# wt12_uart_breakout_board_v21.net
KiCad netlist of a schematic drawn in EAGLE
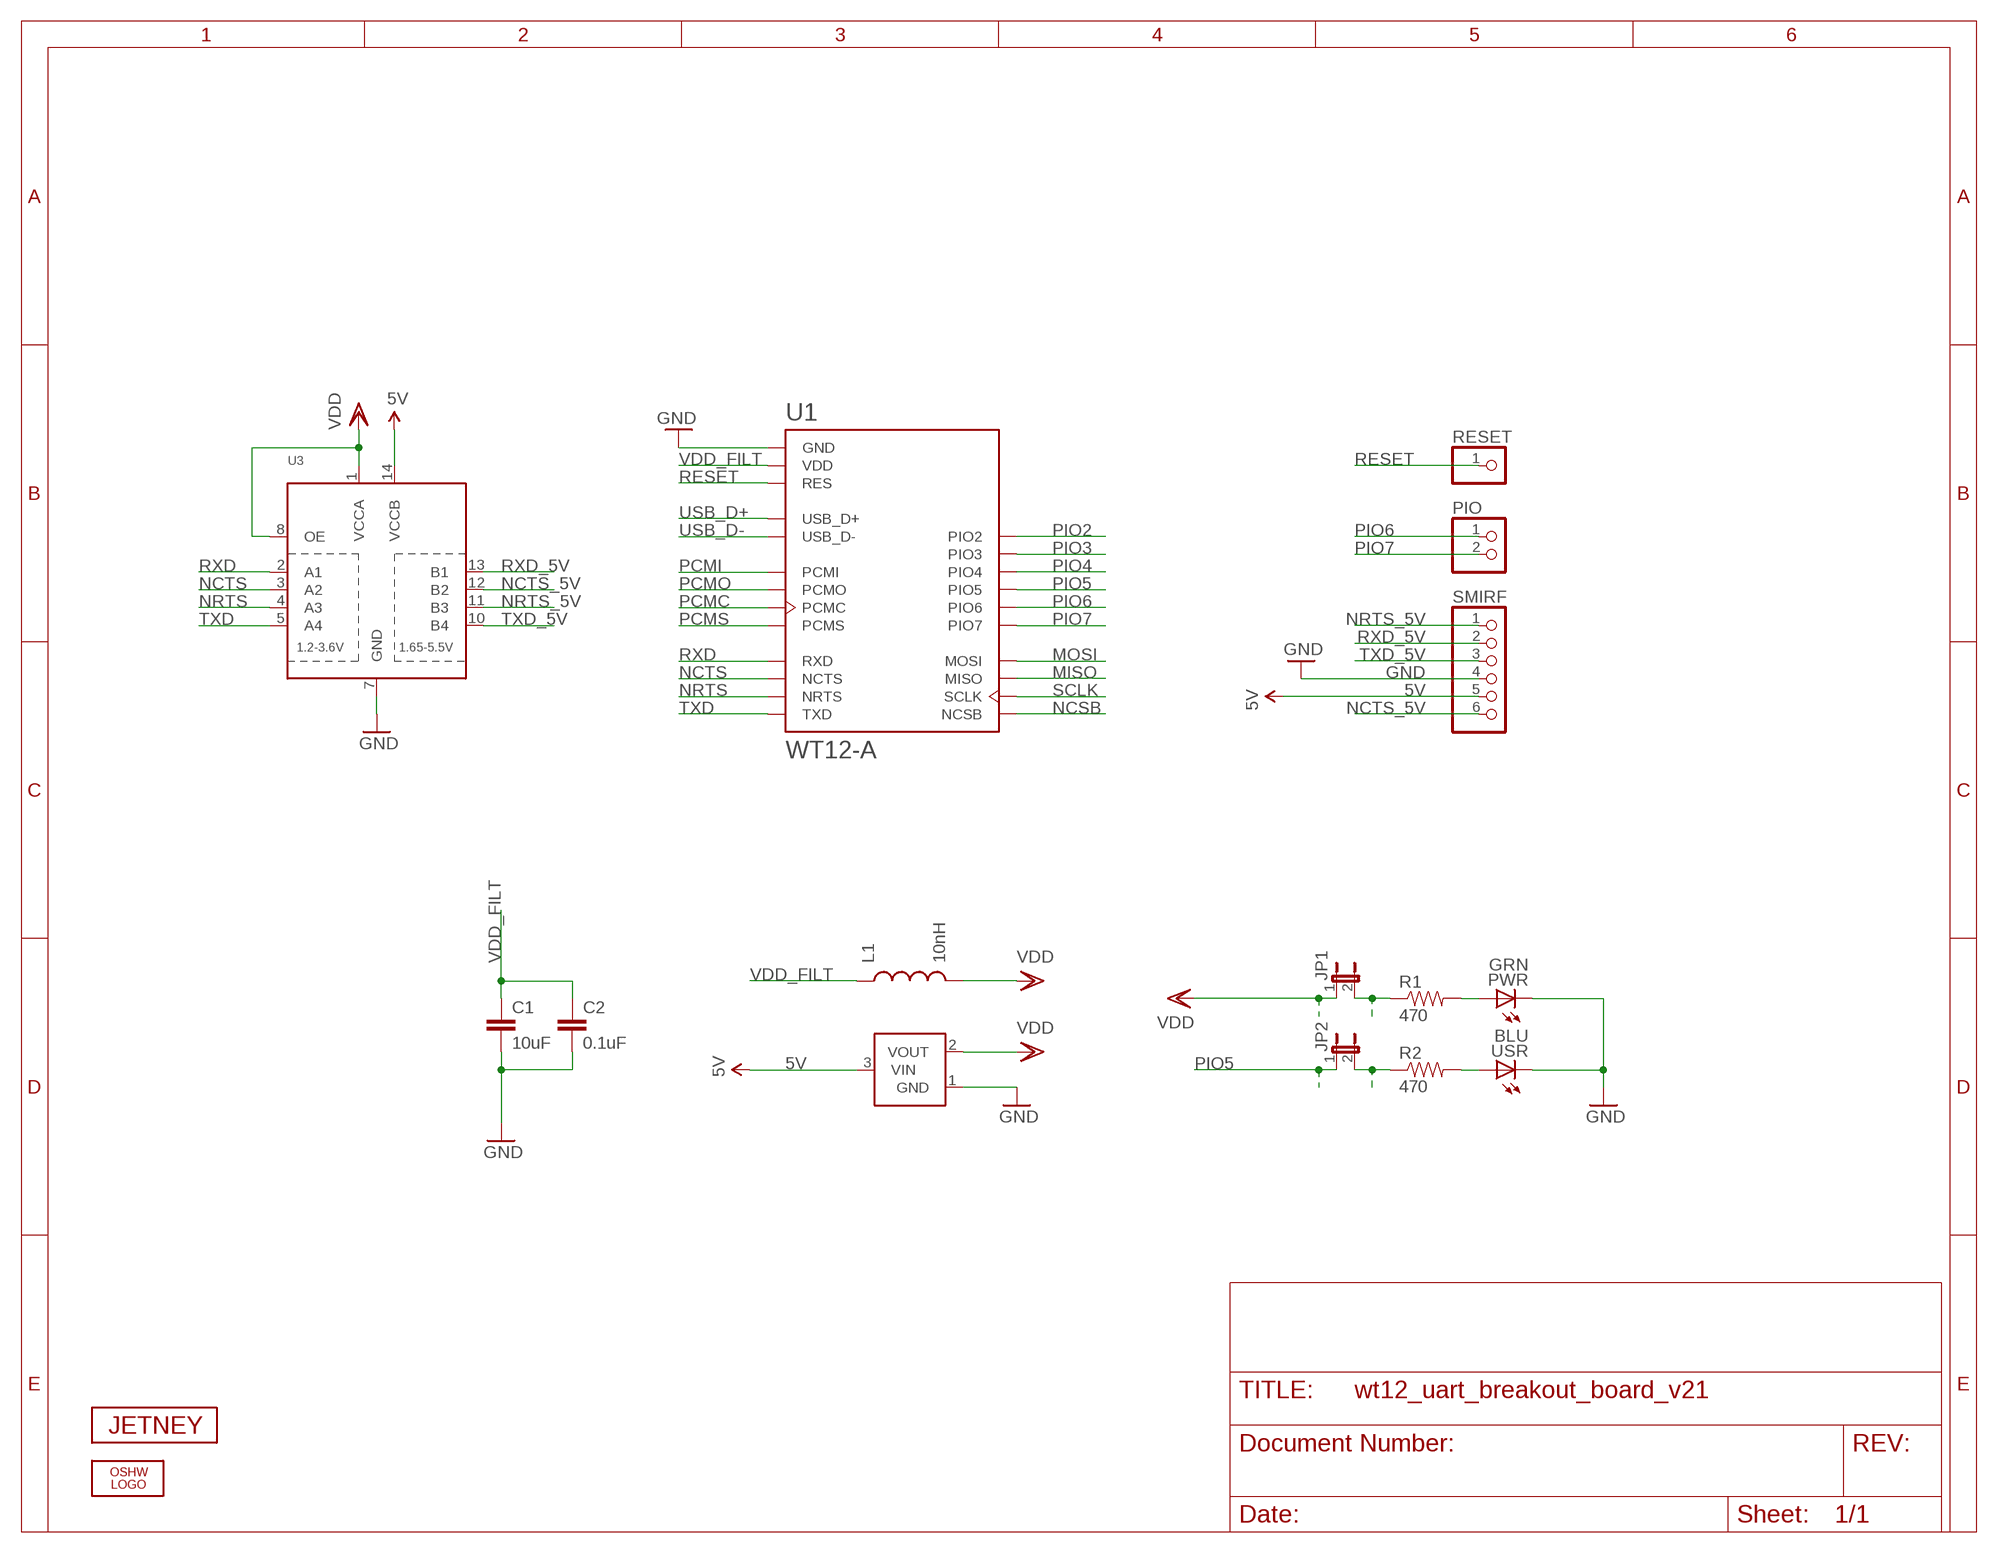
[diagram p0: schematic, sheet 1]

(export (version "E")
  (design (tool "Eeschema 10.0.6"))
  (components
    (comp (ref "C1")
      (value "10uF")
      (footprint "eagle-import:0603-CAP")
      (libsource (lib "eagle-import") (part "CAP0603-CAP"))
    )
    (comp (ref "C2")
      (value "0.1uF")
      (footprint "eagle-import:0603-CAP")
      (libsource (lib "eagle-import") (part "CAP0603-CAP"))
    )
    (comp (ref "JP1")
      (value "JUMPER-2SMD-NC")
      (footprint "eagle-import:SJ_2S")
      (libsource (lib "eagle-import") (part "JUMPER-2SMD-NC"))
    )
    (comp (ref "JP2")
      (value "JUMPER-2SMD-NC")
      (footprint "eagle-import:SJ_2S")
      (libsource (lib "eagle-import") (part "JUMPER-2SMD-NC"))
    )
    (comp (ref "L1")
      (value "10nH")
      (footprint "eagle-import:0603")
      (libsource (lib "eagle-import") (part "INDUCTOR0603"))
    )
    (comp (ref "LOGO1")
      (value "OSHW_LOGO_FILLX0070-NT")
      (footprint "eagle-import:OSHW_FILLX70_NOTEXT")
      (libsource (lib "eagle-import") (part "OSHW_LOGO_FILLX0070-NT"))
    )
    (comp (ref "PIO")
      (value "PINHD-1X2")
      (footprint "eagle-import:1X02")
      (libsource (lib "eagle-import") (part "PINHD-1X2"))
    )
    (comp (ref "PWR")
      (value "GRN")
      (footprint "eagle-import:CHIPLED_0805")
      (libsource (lib "eagle-import") (part "LEDCHIPLED_0805"))
    )
    (comp (ref "R1")
      (value "470")
      (footprint "eagle-import:0603-RES")
      (libsource (lib "eagle-import") (part "RESISTOR0603-RES"))
    )
    (comp (ref "R2")
      (value "470")
      (footprint "eagle-import:0603-RES")
      (libsource (lib "eagle-import") (part "RESISTOR0603-RES"))
    )
    (comp (ref "RESET")
      (value "PINHD-1X1")
      (footprint "eagle-import:1X01")
      (libsource (lib "eagle-import") (part "PINHD-1X1"))
    )
    (comp (ref "SMIRF")
      (value "PINHD-1X6")
      (footprint "eagle-import:1X06")
      (libsource (lib "eagle-import") (part "PINHD-1X6"))
    )
    (comp (ref "U$4")
      (value "JETNEY-LOGO-12")
      (footprint "eagle-import:JETNEY-LOGO-12")
      (libsource (lib "eagle-import") (part "JETNEY-LOGO-12"))
    )
    (comp (ref "U1")
      (value "WT12-A")
      (footprint "eagle-import:WT12-A")
      (libsource (lib "eagle-import") (part "WT12-A"))
    )
    (comp (ref "U2")
      (value "MCP1700")
      (footprint "eagle-import:SOT23-3")
      (libsource (lib "eagle-import") (part "MCP1700"))
    )
    (comp (ref "U3")
      (value "TXB0104PWR")
      (footprint "eagle-import:TSSOP14")
      (libsource (lib "eagle-import") (part "TXB0104PWR"))
    )
    (comp (ref "USR")
      (value "BLU")
      (footprint "eagle-import:CHIPLED_0805")
      (libsource (lib "eagle-import") (part "LEDCHIPLED_0805"))
    )
  )
  (nets
    (net (code "1") (name "/MISO") (class "Default")
      (node (ref "U1") (pin "MISO") (pinfunction "MISO_MISO") (pintype "output"))
    )
    (net (code "2") (name "/MOSI") (class "Default")
      (node (ref "U1") (pin "MOSI") (pinfunction "MOSI_MOSI") (pintype "input"))
    )
    (net (code "3") (name "/NCSB") (class "Default")
      (node (ref "U1") (pin "NCSB") (pinfunction "NCSB_NCSB") (pintype "input"))
    )
    (net (code "4") (name "/NCTS") (class "Default")
      (node (ref "U1") (pin "NCTS") (pinfunction "NCTS_NCTS") (pintype "input"))
      (node (ref "U3") (pin "3") (pinfunction "A2_3") (pintype "bidirectional"))
    )
    (net (code "5") (name "/NCTS_5V") (class "Default")
      (node (ref "SMIRF") (pin "6") (pinfunction "6_6") (pintype "passive"))
      (node (ref "U3") (pin "12") (pinfunction "B2_12") (pintype "bidirectional"))
    )
    (net (code "6") (name "/NRTS") (class "Default")
      (node (ref "U1") (pin "NRTS") (pinfunction "NRTS_NRTS") (pintype "output"))
      (node (ref "U3") (pin "4") (pinfunction "A3_4") (pintype "bidirectional"))
    )
    (net (code "7") (name "/NRTS_5V") (class "Default")
      (node (ref "SMIRF") (pin "1") (pinfunction "1_1") (pintype "passive"))
      (node (ref "U3") (pin "11") (pinfunction "B3_11") (pintype "bidirectional"))
    )
    (net (code "8") (name "/PCMC") (class "Default")
      (node (ref "U1") (pin "PCMC") (pinfunction "PCMC_PCMC") (pintype "bidirectional"))
    )
    (net (code "9") (name "/PCMI") (class "Default")
      (node (ref "U1") (pin "PCMI") (pinfunction "PCMI_PCMI") (pintype "input"))
    )
    (net (code "10") (name "/PCMO") (class "Default")
      (node (ref "U1") (pin "PCMO") (pinfunction "PCMO_PCMO") (pintype "output"))
    )
    (net (code "11") (name "/PCMS") (class "Default")
      (node (ref "U1") (pin "PCMS") (pinfunction "PCMS_PCMS") (pintype "bidirectional"))
    )
    (net (code "12") (name "/PIO2") (class "Default")
      (node (ref "U1") (pin "PIO2") (pinfunction "PIO2_PIO2") (pintype "bidirectional"))
    )
    (net (code "13") (name "/PIO3") (class "Default")
      (node (ref "U1") (pin "PIO3") (pinfunction "PIO3_PIO3") (pintype "bidirectional"))
    )
    (net (code "14") (name "/PIO4") (class "Default")
      (node (ref "U1") (pin "PIO4") (pinfunction "PIO4_PIO4") (pintype "bidirectional"))
    )
    (net (code "15") (name "/PIO5") (class "Default")
      (node (ref "JP2") (pin "1") (pinfunction "1_1") (pintype "passive"))
      (node (ref "U1") (pin "PIO5") (pinfunction "PIO5_PIO5") (pintype "bidirectional"))
    )
    (net (code "16") (name "/PIO6") (class "Default")
      (node (ref "PIO") (pin "1") (pinfunction "1_1") (pintype "passive"))
      (node (ref "U1") (pin "PIO6") (pinfunction "PIO6_PIO6") (pintype "bidirectional"))
    )
    (net (code "17") (name "/PIO7") (class "Default")
      (node (ref "PIO") (pin "2") (pinfunction "2_2") (pintype "passive"))
      (node (ref "U1") (pin "PIO7") (pinfunction "PIO7_PIO7") (pintype "bidirectional"))
    )
    (net (code "18") (name "/RESET") (class "Default")
      (node (ref "RESET") (pin "1") (pinfunction "1_1") (pintype "passive"))
      (node (ref "U1") (pin "RES") (pinfunction "RES_RES") (pintype "input"))
    )
    (net (code "19") (name "/RXD") (class "Default")
      (node (ref "U1") (pin "RXD") (pinfunction "RXD_RXD") (pintype "input"))
      (node (ref "U3") (pin "2") (pinfunction "A1_2") (pintype "bidirectional"))
    )
    (net (code "20") (name "/RXD_5V") (class "Default")
      (node (ref "SMIRF") (pin "2") (pinfunction "2_2") (pintype "passive"))
      (node (ref "U3") (pin "13") (pinfunction "B1_13") (pintype "bidirectional"))
    )
    (net (code "21") (name "/SCLK") (class "Default")
      (node (ref "U1") (pin "SCLK") (pinfunction "SCLK_SCLK") (pintype "input"))
    )
    (net (code "22") (name "/TXD") (class "Default")
      (node (ref "U1") (pin "TXD") (pinfunction "TXD_TXD") (pintype "output"))
      (node (ref "U3") (pin "5") (pinfunction "A4_5") (pintype "bidirectional"))
    )
    (net (code "23") (name "/TXD_5V") (class "Default")
      (node (ref "SMIRF") (pin "3") (pinfunction "3_3") (pintype "passive"))
      (node (ref "U3") (pin "10") (pinfunction "B4_10") (pintype "bidirectional"))
    )
    (net (code "24") (name "/USB_D+") (class "Default")
      (node (ref "U1") (pin "USB_D+") (pinfunction "USB_D+_USB_D+") (pintype "bidirectional"))
    )
    (net (code "25") (name "/USB_D-") (class "Default")
      (node (ref "U1") (pin "USB_D-") (pinfunction "USB_D-_USB_D-") (pintype "bidirectional"))
    )
    (net (code "26") (name "/VDD_FILT") (class "Default")
      (node (ref "C1") (pin "1") (pinfunction "1_1") (pintype "passive"))
      (node (ref "C2") (pin "1") (pinfunction "1_1") (pintype "passive"))
      (node (ref "L1") (pin "1") (pinfunction "1_1") (pintype "passive"))
      (node (ref "U1") (pin "VDD") (pinfunction "VDD_VDD") (pintype "power_in"))
      (node (ref "U1") (pin "VDD@2") (pinfunction "VDD_VDD@2") (pintype "power_in"))
    )
    (net (code "27") (name "5V") (class "Default")
      (node (ref "SMIRF") (pin "5") (pinfunction "5_5") (pintype "passive"))
      (node (ref "U2") (pin "3") (pinfunction "VIN_3") (pintype "power_in"))
      (node (ref "U3") (pin "14") (pinfunction "VCCB_14") (pintype "bidirectional"))
    )
    (net (code "28") (name "GND") (class "Default")
      (node (ref "C1") (pin "2") (pinfunction "2_2") (pintype "passive"))
      (node (ref "C2") (pin "2") (pinfunction "2_2") (pintype "passive"))
      (node (ref "PWR") (pin "C") (pinfunction "C_C") (pintype "passive"))
      (node (ref "SMIRF") (pin "4") (pinfunction "4_4") (pintype "passive"))
      (node (ref "U1") (pin "GND") (pinfunction "GND_GND") (pintype "power_in"))
      (node (ref "U1") (pin "GND@2") (pinfunction "GND_GND@2") (pintype "power_in"))
      (node (ref "U1") (pin "GND@3") (pinfunction "GND_GND@3") (pintype "power_in"))
      (node (ref "U1") (pin "GND@4") (pinfunction "GND_GND@4") (pintype "power_in"))
      (node (ref "U2") (pin "1") (pinfunction "GND_1") (pintype "power_in"))
      (node (ref "U3") (pin "7") (pinfunction "GND_7") (pintype "bidirectional"))
      (node (ref "USR") (pin "C") (pinfunction "C_C") (pintype "passive"))
    )
    (net (code "29") (name "Net-(JP1-Pad2)") (class "Default")
      (node (ref "JP1") (pin "2") (pinfunction "2_2") (pintype "passive"))
      (node (ref "R1") (pin "1") (pinfunction "1_1") (pintype "passive"))
    )
    (net (code "30") (name "Net-(JP2-Pad2)") (class "Default")
      (node (ref "JP2") (pin "2") (pinfunction "2_2") (pintype "passive"))
      (node (ref "R2") (pin "1") (pinfunction "1_1") (pintype "passive"))
    )
    (net (code "31") (name "Net-(PWR-PadA)") (class "Default")
      (node (ref "PWR") (pin "A") (pinfunction "A_A") (pintype "passive"))
      (node (ref "R1") (pin "2") (pinfunction "2_2") (pintype "passive"))
    )
    (net (code "32") (name "Net-(R2-Pad2)") (class "Default")
      (node (ref "R2") (pin "2") (pinfunction "2_2") (pintype "passive"))
      (node (ref "USR") (pin "A") (pinfunction "A_A") (pintype "passive"))
    )
    (net (code "33") (name "VDD") (class "Default")
      (node (ref "JP1") (pin "1") (pinfunction "1_1") (pintype "passive"))
      (node (ref "L1") (pin "2") (pinfunction "2_2") (pintype "passive"))
      (node (ref "U2") (pin "2") (pinfunction "VOUT_2") (pintype "power_in"))
      (node (ref "U3") (pin "1") (pinfunction "VCCA_1") (pintype "bidirectional"))
      (node (ref "U3") (pin "8") (pinfunction "OE_8") (pintype "bidirectional"))
    )
  )
)
